# OMNIBUS_EstlCam_board_v3.net
KiCad netlist of a schematic drawn in EAGLE
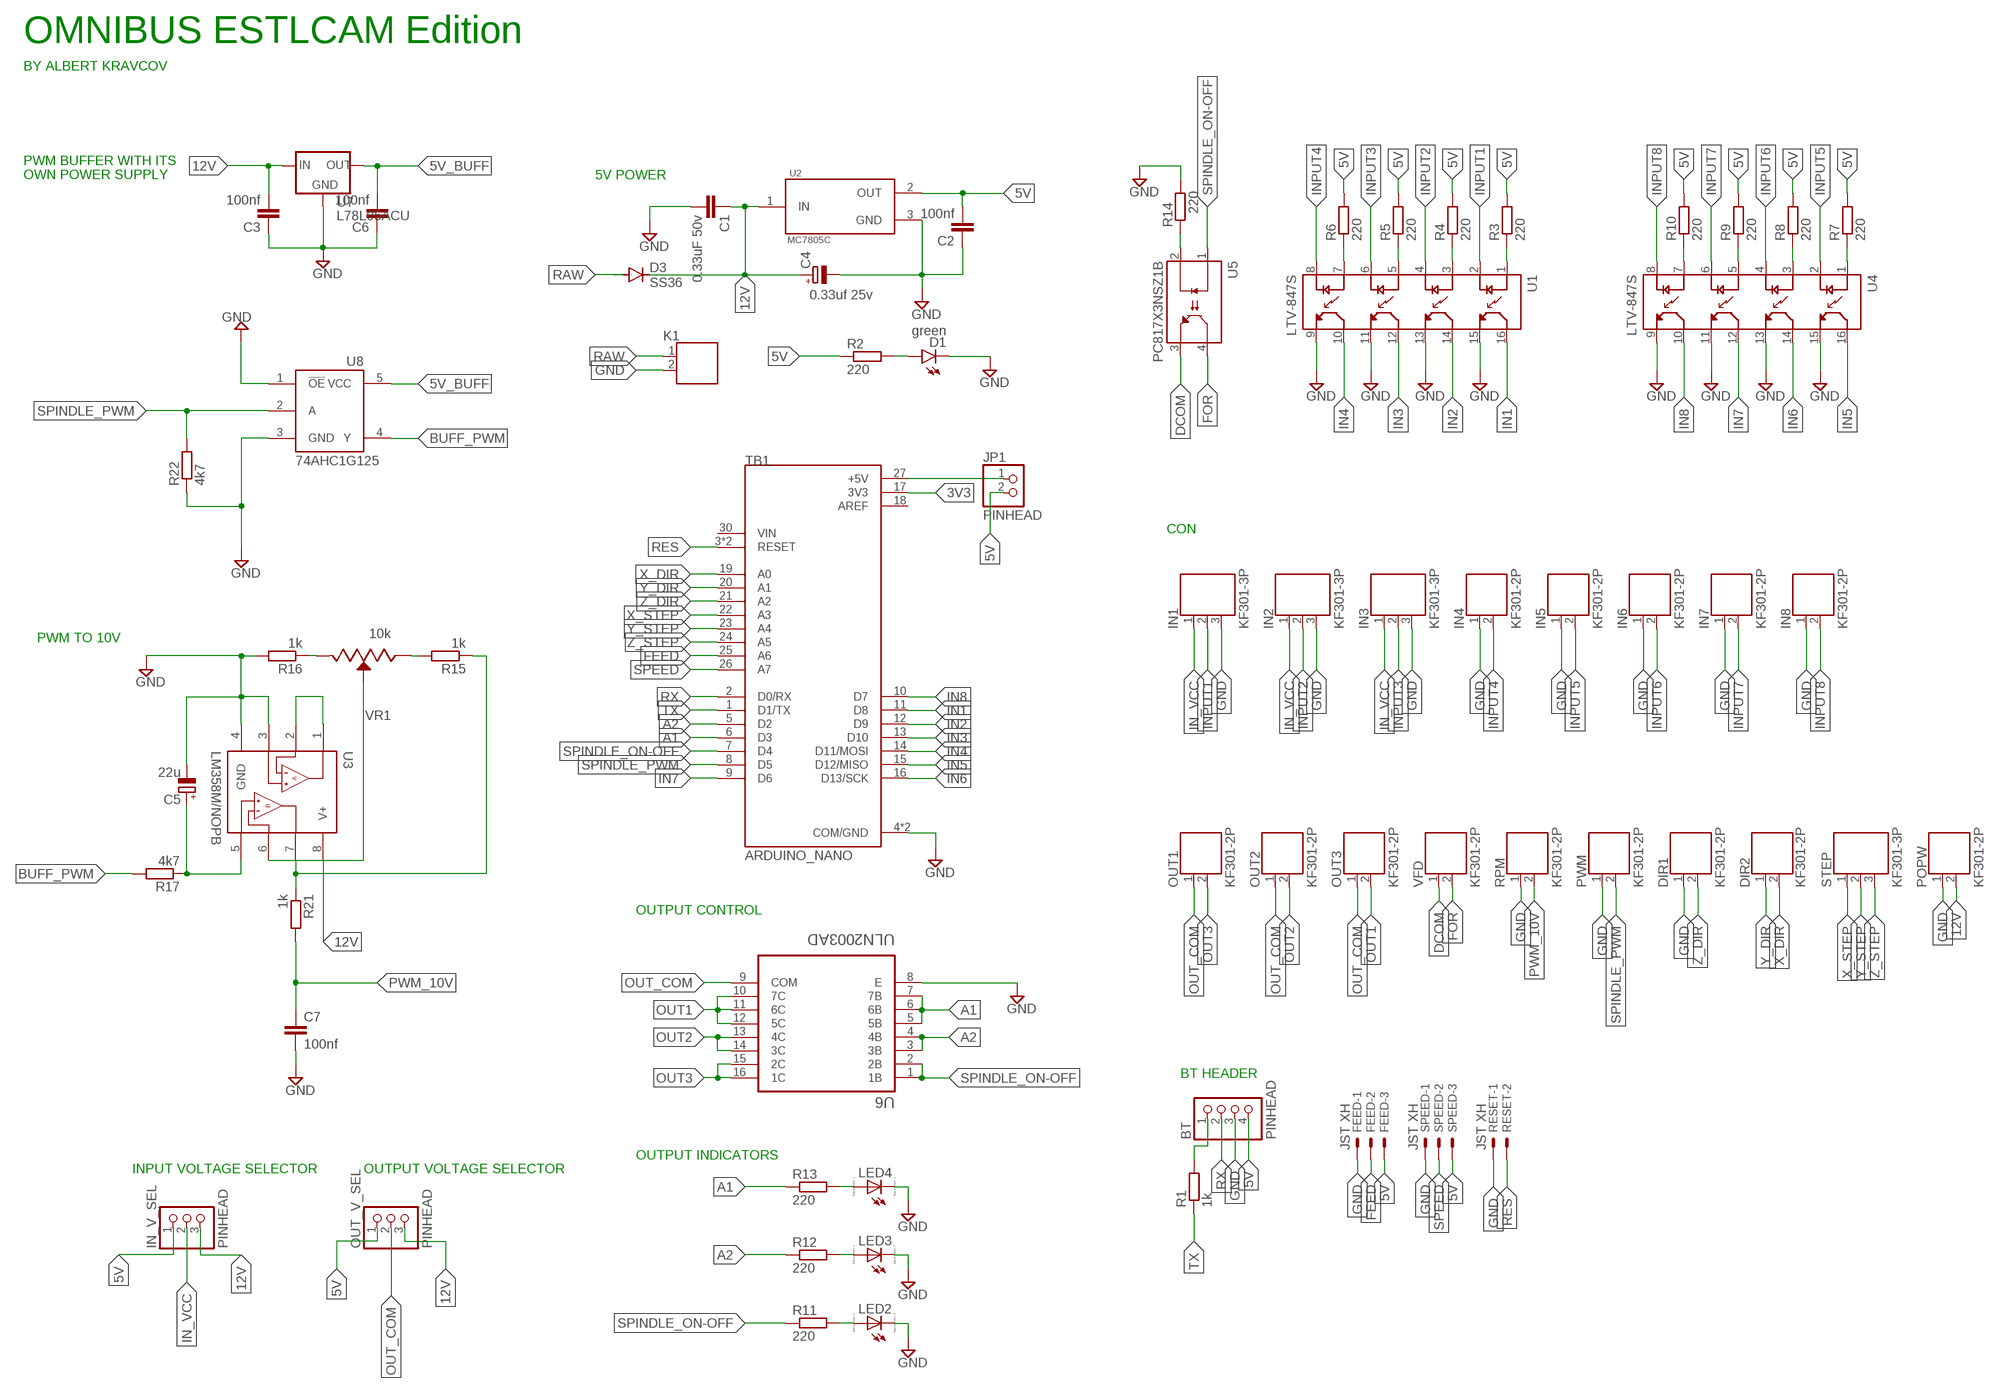
[diagram p0: schematic, sheet 1]

(export (version "E")
  (design (tool "Eeschema 10.0.6"))
  (components
    (comp (ref "BT")
      (value "PINHEAD")
      (footprint "eagle-import:1X04")
      (libsource (lib "eagle-import") (part "PINHD-1X4"))
    )
    (comp (ref "C1")
      (value "0.33uF 50v")
      (footprint "eagle-import:C1206")
      (libsource (lib "eagle-import") (part "C-EUC1206"))
    )
    (comp (ref "C2")
      (value "100nf")
      (footprint "eagle-import:C0805")
      (libsource (lib "eagle-import") (part "C-EUC0805"))
    )
    (comp (ref "C3")
      (value "100nf")
      (footprint "eagle-import:C0805")
      (libsource (lib "eagle-import") (part "C-EUC0805"))
    )
    (comp (ref "C4")
      (value "0.33uf 25v")
      (footprint "eagle-import:E2-5")
      (libsource (lib "eagle-import") (part "CPOL-EUE2-5"))
    )
    (comp (ref "C5")
      (value "22u")
      (footprint "eagle-import:E2-5")
      (libsource (lib "eagle-import") (part "CPOL-EUE2-5"))
    )
    (comp (ref "C6")
      (value "100nf")
      (footprint "eagle-import:C0805")
      (libsource (lib "eagle-import") (part "C-EUC0805"))
    )
    (comp (ref "C7")
      (value "100nf")
      (footprint "eagle-import:C0805")
      (libsource (lib "eagle-import") (part "C-EUC0805"))
    )
    (comp (ref "D1")
      (value "green")
      (footprint "eagle-import:CHIPLED_0805")
      (libsource (lib "eagle-import") (part "LEDCHIPLED_0805"))
    )
    (comp (ref "D3")
      (value "SS36")
      (footprint "eagle-import:SMB")
      (libsource (lib "eagle-import") (part "ES2D"))
    )
    (comp (ref "DIR1")
      (value "KF301-2P")
      (footprint "eagle-import:691131710002")
      (libsource (lib "eagle-import") (part "691131710002"))
    )
    (comp (ref "DIR2")
      (value "KF301-2P")
      (footprint "eagle-import:691131710002")
      (libsource (lib "eagle-import") (part "691131710002"))
    )
    (comp (ref "FEED")
      (value "JST XH")
      (footprint "eagle-import:22-23-2031")
      (fields (field (name "MF") "MOLEX") (field (name "MPN") "22-23-2031"))
      (libsource (lib "eagle-import") (part "22-23-2031"))
    )
    (comp (ref "IN1")
      (value "KF301-3P")
      (footprint "eagle-import:691131710003")
      (libsource (lib "eagle-import") (part "691131710003"))
    )
    (comp (ref "IN2")
      (value "KF301-3P")
      (footprint "eagle-import:691131710003")
      (libsource (lib "eagle-import") (part "691131710003"))
    )
    (comp (ref "IN3")
      (value "KF301-3P")
      (footprint "eagle-import:691131710003")
      (libsource (lib "eagle-import") (part "691131710003"))
    )
    (comp (ref "IN4")
      (value "KF301-2P")
      (footprint "eagle-import:691131710002")
      (libsource (lib "eagle-import") (part "691131710002"))
    )
    (comp (ref "IN5")
      (value "KF301-2P")
      (footprint "eagle-import:691131710002")
      (libsource (lib "eagle-import") (part "691131710002"))
    )
    (comp (ref "IN6")
      (value "KF301-2P")
      (footprint "eagle-import:691131710002")
      (libsource (lib "eagle-import") (part "691131710002"))
    )
    (comp (ref "IN7")
      (value "KF301-2P")
      (footprint "eagle-import:691131710002")
      (libsource (lib "eagle-import") (part "691131710002"))
    )
    (comp (ref "IN8")
      (value "KF301-2P")
      (footprint "eagle-import:691131710002")
      (libsource (lib "eagle-import") (part "691131710002"))
    )
    (comp (ref "IN_V_SEL")
      (value "PINHEAD")
      (footprint "eagle-import:1X03")
      (libsource (lib "eagle-import") (part "PINHD-1X3"))
    )
    (comp (ref "JP1")
      (value "PINHEAD")
      (footprint "eagle-import:1X02")
      (libsource (lib "eagle-import") (part "PINHD-1X2"))
    )
    (comp (ref "K1")
      (value "691131710002")
      (footprint "eagle-import:691131710002")
      (libsource (lib "eagle-import") (part "691131710002"))
    )
    (comp (ref "LED2")
      (value "LED_ESML0603")
      (footprint "eagle-import:LED_SML0603")
      (libsource (lib "eagle-import") (part "LED_ESML0603"))
    )
    (comp (ref "LED3")
      (value "LED_ESML0603")
      (footprint "eagle-import:LED_SML0603")
      (libsource (lib "eagle-import") (part "LED_ESML0603"))
    )
    (comp (ref "LED4")
      (value "LED_ESML0603")
      (footprint "eagle-import:LED_SML0603")
      (libsource (lib "eagle-import") (part "LED_ESML0603"))
    )
    (comp (ref "OUT1")
      (value "KF301-2P")
      (footprint "eagle-import:691131710002")
      (libsource (lib "eagle-import") (part "691131710002"))
    )
    (comp (ref "OUT2")
      (value "KF301-2P")
      (footprint "eagle-import:691131710002")
      (libsource (lib "eagle-import") (part "691131710002"))
    )
    (comp (ref "OUT3")
      (value "KF301-2P")
      (footprint "eagle-import:691131710002")
      (libsource (lib "eagle-import") (part "691131710002"))
    )
    (comp (ref "OUT_V_SEL")
      (value "PINHEAD")
      (footprint "eagle-import:1X03")
      (libsource (lib "eagle-import") (part "PINHD-1X3"))
    )
    (comp (ref "POPW")
      (value "KF301-2P")
      (footprint "eagle-import:691131710002")
      (libsource (lib "eagle-import") (part "691131710002"))
    )
    (comp (ref "PWM")
      (value "KF301-2P")
      (footprint "eagle-import:691131710002")
      (libsource (lib "eagle-import") (part "691131710002"))
    )
    (comp (ref "R1")
      (value "1k")
      (footprint "eagle-import:R0805")
      (libsource (lib "eagle-import") (part "R-EU_R0805"))
    )
    (comp (ref "R2")
      (value "220")
      (footprint "eagle-import:R0805")
      (libsource (lib "eagle-import") (part "R-EU_R0805"))
    )
    (comp (ref "R3")
      (value "220")
      (footprint "eagle-import:R0805")
      (libsource (lib "eagle-import") (part "R-EU_R0805"))
    )
    (comp (ref "R4")
      (value "220")
      (footprint "eagle-import:R0805")
      (libsource (lib "eagle-import") (part "R-EU_R0805"))
    )
    (comp (ref "R5")
      (value "220")
      (footprint "eagle-import:R0805")
      (libsource (lib "eagle-import") (part "R-EU_R0805"))
    )
    (comp (ref "R6")
      (value "220")
      (footprint "eagle-import:R0805")
      (libsource (lib "eagle-import") (part "R-EU_R0805"))
    )
    (comp (ref "R7")
      (value "220")
      (footprint "eagle-import:R0805")
      (libsource (lib "eagle-import") (part "R-EU_R0805"))
    )
    (comp (ref "R8")
      (value "220")
      (footprint "eagle-import:R0805")
      (libsource (lib "eagle-import") (part "R-EU_R0805"))
    )
    (comp (ref "R9")
      (value "220")
      (footprint "eagle-import:R0805")
      (libsource (lib "eagle-import") (part "R-EU_R0805"))
    )
    (comp (ref "R10")
      (value "220")
      (footprint "eagle-import:R0805")
      (libsource (lib "eagle-import") (part "R-EU_R0805"))
    )
    (comp (ref "R11")
      (value "220")
      (footprint "eagle-import:R0603")
      (libsource (lib "eagle-import") (part "R-EU_R0603"))
    )
    (comp (ref "R12")
      (value "220")
      (footprint "eagle-import:R0603")
      (libsource (lib "eagle-import") (part "R-EU_R0603"))
    )
    (comp (ref "R13")
      (value "220")
      (footprint "eagle-import:R0603")
      (libsource (lib "eagle-import") (part "R-EU_R0603"))
    )
    (comp (ref "R14")
      (value "220")
      (footprint "eagle-import:R0805")
      (libsource (lib "eagle-import") (part "R-EU_R0805"))
    )
    (comp (ref "R15")
      (value "1k")
      (footprint "eagle-import:R0805")
      (libsource (lib "eagle-import") (part "R-EU_R0805"))
    )
    (comp (ref "R16")
      (value "1k")
      (footprint "eagle-import:R0805")
      (libsource (lib "eagle-import") (part "R-EU_R0805"))
    )
    (comp (ref "R17")
      (value "4k7")
      (footprint "eagle-import:R0603")
      (libsource (lib "eagle-import") (part "R-EU_R0603"))
    )
    (comp (ref "R21")
      (value "1k")
      (footprint "eagle-import:R0805")
      (libsource (lib "eagle-import") (part "R-EU_R0805"))
    )
    (comp (ref "R22")
      (value "4k7")
      (footprint "eagle-import:R0805")
      (libsource (lib "eagle-import") (part "R-EU_R0805"))
    )
    (comp (ref "RESET")
      (value "JST XH")
      (footprint "eagle-import:22-23-2021")
      (fields (field (name "MF") "MOLEX") (field (name "MPN") "22-23-2021"))
      (libsource (lib "eagle-import") (part "22-23-2021"))
    )
    (comp (ref "RPM")
      (value "KF301-2P")
      (footprint "eagle-import:691131710002")
      (libsource (lib "eagle-import") (part "691131710002"))
    )
    (comp (ref "SPEED")
      (value "JST XH")
      (footprint "eagle-import:22-23-2031")
      (fields (field (name "MF") "MOLEX") (field (name "MPN") "22-23-2031"))
      (libsource (lib "eagle-import") (part "22-23-2031"))
    )
    (comp (ref "STEP")
      (value "KF301-3P")
      (footprint "eagle-import:691131710003")
      (libsource (lib "eagle-import") (part "691131710003"))
    )
    (comp (ref "TB1")
      (value "ARDUINO_NANO")
      (footprint "eagle-import:SHIELD_ARDUINO_NANO")
      (fields (field (name "MF") "Arduino") (field (name "MP") "ARDUINO NANO"))
      (libsource (lib "eagle-import") (part "ARDUINO_NANO"))
    )
    (comp (ref "U1")
      (value "LTV-847S")
      (footprint "eagle-import:SOIC254P1016X460-16N")
      (fields (field (name "MF") "Lite-On Inc."))
      (libsource (lib "eagle-import") (part "LTV-847S"))
    )
    (comp (ref "U2")
      (value "MC7805C")
      (footprint "eagle-import:TO254P1515X470-3N")
      (fields (field (name "MF") "STMicroelectronics") (field (name "MP") "L7805ACD2T-TR"))
      (libsource (lib "eagle-import") (part "L7805ACD2T-TR"))
    )
    (comp (ref "U3")
      (value "LM358M/NOPB")
      (footprint "eagle-import:SOIC127P599X175-8N")
      (fields (field (name "MF") "Texas Instruments") (field (name "MP") "LM358M"))
      (libsource (lib "eagle-import") (part "LM358M/NOPB"))
    )
    (comp (ref "U4")
      (value "LTV-847S")
      (footprint "eagle-import:SOIC254P1016X460-16N")
      (fields (field (name "MF") "Lite-On Inc."))
      (libsource (lib "eagle-import") (part "LTV-847S"))
    )
    (comp (ref "U5")
      (value "PC817X3NSZ1B")
      (footprint "eagle-import:DIP762W50P254L495H455Q4")
      (fields (field (name "MF") "Sharp Microelectronics"))
      (libsource (lib "eagle-import") (part "PC817X3NSZ1B"))
    )
    (comp (ref "U6")
      (value "ULN2003AD")
      (footprint "eagle-import:SOIC127P600X175-16N")
      (fields (field (name "MF") "Texas Instruments"))
      (libsource (lib "eagle-import") (part "ULN2003AD"))
    )
    (comp (ref "U7")
      (value "L78L05ACU")
      (footprint "eagle-import:SOT89")
      (fields (field (name "MF") "STMicroelectronics"))
      (libsource (lib "eagle-import") (part "L78L05ACU"))
    )
    (comp (ref "U8")
      (value "74AHC1G125")
      (footprint "eagle-import:SOT23-5L")
      (fields (field (name "MF") "Texas Instruments"))
      (libsource (lib "eagle-import") (part "74AHC1G125"))
    )
    (comp (ref "VFD")
      (value "KF301-2P")
      (footprint "eagle-import:691131710002")
      (libsource (lib "eagle-import") (part "691131710002"))
    )
    (comp (ref "VR1")
      (value "10k")
      (footprint "eagle-import:TRIM_3296W-1-502")
      (fields (field (name "MF") "Bourns") (field (name "MP") "3296W-1-502"))
      (libsource (lib "eagle-import") (part "3296W-1-502"))
    )
  )
  (nets
    (net (code "1") (name "/AREF") (class "Default")
      (node (ref "TB1") (pin "18") (pinfunction "AREF_18") (pintype "power_in"))
    )
    (net (code "2") (name "3V3") (class "Default")
      (node (ref "TB1") (pin "17") (pinfunction "3V3_17") (pintype "power_in"))
    )
    (net (code "3") (name "5V") (class "Default")
      (node (ref "BT") (pin "4") (pinfunction "4_4") (pintype "passive"))
      (node (ref "C2") (pin "2") (pinfunction "2_2") (pintype "passive"))
      (node (ref "FEED") (pin "3") (pinfunction "S_3") (pintype "passive"))
      (node (ref "IN_V_SEL") (pin "1") (pinfunction "1_1") (pintype "passive"))
      (node (ref "JP1") (pin "2") (pinfunction "2_2") (pintype "passive"))
      (node (ref "OUT_V_SEL") (pin "1") (pinfunction "1_1") (pintype "passive"))
      (node (ref "R10") (pin "2") (pinfunction "2_2") (pintype "passive"))
      (node (ref "R2") (pin "1") (pinfunction "1_1") (pintype "passive"))
      (node (ref "R3") (pin "2") (pinfunction "2_2") (pintype "passive"))
      (node (ref "R4") (pin "2") (pinfunction "2_2") (pintype "passive"))
      (node (ref "R5") (pin "2") (pinfunction "2_2") (pintype "passive"))
      (node (ref "R6") (pin "2") (pinfunction "2_2") (pintype "passive"))
      (node (ref "R7") (pin "2") (pinfunction "2_2") (pintype "passive"))
      (node (ref "R8") (pin "2") (pinfunction "2_2") (pintype "passive"))
      (node (ref "R9") (pin "2") (pinfunction "2_2") (pintype "passive"))
      (node (ref "SPEED") (pin "3") (pinfunction "S_3") (pintype "passive"))
      (node (ref "U2") (pin "2") (pinfunction "OUT_2") (pintype "output"))
    )
    (net (code "4") (name "5V_BUFF") (class "Default")
      (node (ref "C6") (pin "2") (pinfunction "2_2") (pintype "passive"))
      (node (ref "U7") (pin "1") (pinfunction "OUT_1") (pintype "output"))
      (node (ref "U8") (pin "5") (pinfunction "VCC_5") (pintype "power_in"))
    )
    (net (code "5") (name "12V") (class "Default")
      (node (ref "C1") (pin "1") (pinfunction "1_1") (pintype "passive"))
      (node (ref "C3") (pin "2") (pinfunction "2_2") (pintype "passive"))
      (node (ref "C4") (pin "+") (pinfunction "+_+") (pintype "passive"))
      (node (ref "D3") (pin "C") (pinfunction "C_C") (pintype "passive"))
      (node (ref "IN_V_SEL") (pin "3") (pinfunction "3_3") (pintype "passive"))
      (node (ref "OUT_V_SEL") (pin "3") (pinfunction "3_3") (pintype "passive"))
      (node (ref "POPW") (pin "2") (pinfunction "2_2") (pintype "passive"))
      (node (ref "U2") (pin "1") (pinfunction "IN_1") (pintype "input"))
      (node (ref "U3") (pin "8") (pinfunction "V+_8") (pintype "power_in"))
      (node (ref "U7") (pin "3") (pinfunction "IN_3") (pintype "input"))
    )
    (net (code "6") (name "A1") (class "Default")
      (node (ref "R13") (pin "1") (pinfunction "1_1") (pintype "passive"))
      (node (ref "TB1") (pin "6") (pinfunction "D3_6") (pintype "bidirectional"))
      (node (ref "U6") (pin "5") (pinfunction "5B_5") (pintype "input"))
      (node (ref "U6") (pin "6") (pinfunction "6B_6") (pintype "input"))
      (node (ref "U6") (pin "7") (pinfunction "7B_7") (pintype "input"))
    )
    (net (code "7") (name "A2") (class "Default")
      (node (ref "R12") (pin "1") (pinfunction "1_1") (pintype "passive"))
      (node (ref "TB1") (pin "5") (pinfunction "D2_5") (pintype "bidirectional"))
      (node (ref "U6") (pin "3") (pinfunction "3B_3") (pintype "input"))
      (node (ref "U6") (pin "4") (pinfunction "4B_4") (pintype "input"))
    )
    (net (code "8") (name "BUFF_PWM") (class "Default")
      (node (ref "R17") (pin "2") (pinfunction "2_2") (pintype "passive"))
      (node (ref "U8") (pin "4") (pinfunction "Y_4") (pintype "output"))
    )
    (net (code "9") (name "DCOM") (class "Default")
      (node (ref "U5") (pin "3") (pinfunction "EMITTER_3") (pintype "passive"))
      (node (ref "VFD") (pin "1") (pinfunction "1_1") (pintype "passive"))
    )
    (net (code "10") (name "FEED") (class "Default")
      (node (ref "FEED") (pin "2") (pinfunction "S_2") (pintype "passive"))
      (node (ref "TB1") (pin "25") (pinfunction "A6_25") (pintype "input"))
    )
    (net (code "11") (name "FOR") (class "Default")
      (node (ref "U5") (pin "4") (pinfunction "COLLECTOR_4") (pintype "passive"))
      (node (ref "VFD") (pin "2") (pinfunction "2_2") (pintype "passive"))
    )
    (net (code "12") (name "GND") (class "Default")
      (node (ref "BT") (pin "3") (pinfunction "3_3") (pintype "passive"))
      (node (ref "C1") (pin "2") (pinfunction "2_2") (pintype "passive"))
      (node (ref "C2") (pin "1") (pinfunction "1_1") (pintype "passive"))
      (node (ref "C3") (pin "1") (pinfunction "1_1") (pintype "passive"))
      (node (ref "C4") (pin "-") (pinfunction "-_-") (pintype "passive"))
      (node (ref "C5") (pin "-") (pinfunction "-_-") (pintype "passive"))
      (node (ref "C6") (pin "1") (pinfunction "1_1") (pintype "passive"))
      (node (ref "C7") (pin "2") (pinfunction "2_2") (pintype "passive"))
      (node (ref "D1") (pin "C") (pinfunction "C_C") (pintype "passive"))
      (node (ref "DIR1") (pin "1") (pinfunction "1_1") (pintype "passive"))
      (node (ref "FEED") (pin "1") (pinfunction "S_1") (pintype "passive"))
      (node (ref "IN1") (pin "3") (pinfunction "3_3") (pintype "passive"))
      (node (ref "IN2") (pin "3") (pinfunction "3_3") (pintype "passive"))
      (node (ref "IN3") (pin "3") (pinfunction "3_3") (pintype "passive"))
      (node (ref "IN4") (pin "1") (pinfunction "1_1") (pintype "passive"))
      (node (ref "IN5") (pin "1") (pinfunction "1_1") (pintype "passive"))
      (node (ref "IN6") (pin "1") (pinfunction "1_1") (pintype "passive"))
      (node (ref "IN7") (pin "1") (pinfunction "1_1") (pintype "passive"))
      (node (ref "IN8") (pin "1") (pinfunction "1_1") (pintype "passive"))
      (node (ref "K1") (pin "2") (pinfunction "2_2") (pintype "passive"))
      (node (ref "LED2") (pin "C") (pinfunction "C_C") (pintype "passive"))
      (node (ref "LED3") (pin "C") (pinfunction "C_C") (pintype "passive"))
      (node (ref "LED4") (pin "C") (pinfunction "C_C") (pintype "passive"))
      (node (ref "POPW") (pin "1") (pinfunction "1_1") (pintype "passive"))
      (node (ref "PWM") (pin "1") (pinfunction "1_1") (pintype "passive"))
      (node (ref "R14") (pin "2") (pinfunction "2_2") (pintype "passive"))
      (node (ref "R16") (pin "2") (pinfunction "2_2") (pintype "passive"))
      (node (ref "R22") (pin "1") (pinfunction "1_1") (pintype "passive"))
      (node (ref "RESET") (pin "1") (pinfunction "S_1") (pintype "passive"))
      (node (ref "RPM") (pin "1") (pinfunction "1_1") (pintype "passive"))
      (node (ref "SPEED") (pin "1") (pinfunction "S_1") (pintype "passive"))
      (node (ref "TB1") (pin "29") (pinfunction "COM/GND_29") (pintype "power_in"))
      (node (ref "TB1") (pin "4") (pinfunction "COM/GND_4") (pintype "power_in"))
      (node (ref "U1") (pin "11") (pinfunction "ET2_11") (pintype "passive"))
      (node (ref "U1") (pin "13") (pinfunction "ET1_13") (pintype "passive"))
      (node (ref "U1") (pin "15") (pinfunction "ET_15") (pintype "passive"))
      (node (ref "U1") (pin "9") (pinfunction "ET3_9") (pintype "passive"))
      (node (ref "U2") (pin "3") (pinfunction "GND_3") (pintype "power_in"))
      (node (ref "U3") (pin "3") (pinfunction "+INA_3") (pintype "input"))
      (node (ref "U3") (pin "4") (pinfunction "GND_4") (pintype "power_in"))
      (node (ref "U4") (pin "11") (pinfunction "ET2_11") (pintype "passive"))
      (node (ref "U4") (pin "13") (pinfunction "ET1_13") (pintype "passive"))
      (node (ref "U4") (pin "15") (pinfunction "ET_15") (pintype "passive"))
      (node (ref "U4") (pin "9") (pinfunction "ET3_9") (pintype "passive"))
      (node (ref "U6") (pin "8") (pinfunction "E_8") (pintype "input"))
      (node (ref "U7") (pin "2") (pinfunction "GND_2") (pintype "input"))
      (node (ref "U8") (pin "1") (pinfunction "~{OE}_1") (pintype "input"))
      (node (ref "U8") (pin "3") (pinfunction "GND_3") (pintype "power_in"))
    )
    (net (code "13") (name "IN1") (class "Default")
      (node (ref "TB1") (pin "11") (pinfunction "D8_11") (pintype "bidirectional"))
      (node (ref "U1") (pin "16") (pinfunction "CT_16") (pintype "passive"))
    )
    (net (code "14") (name "IN2") (class "Default")
      (node (ref "TB1") (pin "12") (pinfunction "D9_12") (pintype "bidirectional"))
      (node (ref "U1") (pin "14") (pinfunction "CT1_14") (pintype "passive"))
    )
    (net (code "15") (name "IN3") (class "Default")
      (node (ref "TB1") (pin "13") (pinfunction "D10_13") (pintype "bidirectional"))
      (node (ref "U1") (pin "12") (pinfunction "CT2_12") (pintype "passive"))
    )
    (net (code "16") (name "IN4") (class "Default")
      (node (ref "TB1") (pin "14") (pinfunction "D11/MOSI_14") (pintype "bidirectional"))
      (node (ref "U1") (pin "10") (pinfunction "CT3_10") (pintype "passive"))
    )
    (net (code "17") (name "IN5") (class "Default")
      (node (ref "TB1") (pin "15") (pinfunction "D12/MISO_15") (pintype "bidirectional"))
      (node (ref "U4") (pin "16") (pinfunction "CT_16") (pintype "passive"))
    )
    (net (code "18") (name "IN6") (class "Default")
      (node (ref "TB1") (pin "16") (pinfunction "D13/SCK_16") (pintype "bidirectional"))
      (node (ref "U4") (pin "14") (pinfunction "CT1_14") (pintype "passive"))
    )
    (net (code "19") (name "IN7") (class "Default")
      (node (ref "TB1") (pin "9") (pinfunction "D6_9") (pintype "bidirectional"))
      (node (ref "U4") (pin "12") (pinfunction "CT2_12") (pintype "passive"))
    )
    (net (code "20") (name "IN8") (class "Default")
      (node (ref "TB1") (pin "10") (pinfunction "D7_10") (pintype "bidirectional"))
      (node (ref "U4") (pin "10") (pinfunction "CT3_10") (pintype "passive"))
    )
    (net (code "21") (name "INPUT1") (class "Default")
      (node (ref "IN1") (pin "2") (pinfunction "2_2") (pintype "passive"))
      (node (ref "U1") (pin "2") (pinfunction "C_2") (pintype "passive"))
    )
    (net (code "22") (name "INPUT2") (class "Default")
      (node (ref "IN2") (pin "2") (pinfunction "2_2") (pintype "passive"))
      (node (ref "U1") (pin "4") (pinfunction "C1_4") (pintype "passive"))
    )
    (net (code "23") (name "INPUT3") (class "Default")
      (node (ref "IN3") (pin "2") (pinfunction "2_2") (pintype "passive"))
      (node (ref "U1") (pin "6") (pinfunction "C2_6") (pintype "passive"))
    )
    (net (code "24") (name "INPUT4") (class "Default")
      (node (ref "IN4") (pin "2") (pinfunction "2_2") (pintype "passive"))
      (node (ref "U1") (pin "8") (pinfunction "C3_8") (pintype "passive"))
    )
    (net (code "25") (name "INPUT5") (class "Default")
      (node (ref "IN5") (pin "2") (pinfunction "2_2") (pintype "passive"))
      (node (ref "U4") (pin "2") (pinfunction "C_2") (pintype "passive"))
    )
    (net (code "26") (name "INPUT6") (class "Default")
      (node (ref "IN6") (pin "2") (pinfunction "2_2") (pintype "passive"))
      (node (ref "U4") (pin "4") (pinfunction "C1_4") (pintype "passive"))
    )
    (net (code "27") (name "INPUT7") (class "Default")
      (node (ref "IN7") (pin "2") (pinfunction "2_2") (pintype "passive"))
      (node (ref "U4") (pin "6") (pinfunction "C2_6") (pintype "passive"))
    )
    (net (code "28") (name "INPUT8") (class "Default")
      (node (ref "IN8") (pin "2") (pinfunction "2_2") (pintype "passive"))
      (node (ref "U4") (pin "8") (pinfunction "C3_8") (pintype "passive"))
    )
    (net (code "29") (name "IN_VCC") (class "Default")
      (node (ref "IN1") (pin "1") (pinfunction "1_1") (pintype "passive"))
      (node (ref "IN2") (pin "1") (pinfunction "1_1") (pintype "passive"))
      (node (ref "IN3") (pin "1") (pinfunction "1_1") (pintype "passive"))
      (node (ref "IN_V_SEL") (pin "2") (pinfunction "2_2") (pintype "passive"))
    )
    (net (code "30") (name "Net-(BT-Pad1)") (class "Default")
      (node (ref "BT") (pin "1") (pinfunction "1_1") (pintype "passive"))
      (node (ref "R1") (pin "2") (pinfunction "2_2") (pintype "passive"))
    )
    (net (code "31") (name "Net-(D1-PadA)") (class "Default")
      (node (ref "D1") (pin "A") (pinfunction "A_A") (pintype "passive"))
      (node (ref "R2") (pin "2") (pinfunction "2_2") (pintype "passive"))
    )
    (net (code "32") (name "Net-(LED2-PadA)") (class "Default")
      (node (ref "LED2") (pin "A") (pinfunction "A_A") (pintype "passive"))
      (node (ref "R11") (pin "2") (pinfunction "2_2") (pintype "passive"))
    )
    (net (code "33") (name "Net-(LED3-PadA)") (class "Default")
      (node (ref "LED3") (pin "A") (pinfunction "A_A") (pintype "passive"))
      (node (ref "R12") (pin "2") (pinfunction "2_2") (pintype "passive"))
    )
    (net (code "34") (name "Net-(LED4-PadA)") (class "Default")
      (node (ref "LED4") (pin "A") (pinfunction "A_A") (pintype "passive"))
      (node (ref "R13") (pin "2") (pinfunction "2_2") (pintype "passive"))
    )
    (net (code "35") (name "Net-(TB1-+5V)") (class "Default")
      (node (ref "JP1") (pin "1") (pinfunction "1_1") (pintype "passive"))
      (node (ref "TB1") (pin "27") (pinfunction "+5V_27") (pintype "power_in"))
    )
    (net (code "36") (name "Net-(U1-A)") (class "Default")
      (node (ref "R3") (pin "1") (pinfunction "1_1") (pintype "passive"))
      (node (ref "U1") (pin "1") (pinfunction "A_1") (pintype "passive"))
    )
    (net (code "37") (name "Net-(U1-A1)") (class "Default")
      (node (ref "R4") (pin "1") (pinfunction "1_1") (pintype "passive"))
      (node (ref "U1") (pin "3") (pinfunction "A1_3") (pintype "passive"))
    )
    (net (code "38") (name "Net-(U1-A2)") (class "Default")
      (node (ref "R5") (pin "1") (pinfunction "1_1") (pintype "passive"))
      (node (ref "U1") (pin "5") (pinfunction "A2_5") (pintype "passive"))
    )
    (net (code "39") (name "Net-(U1-A3)") (class "Default")
      (node (ref "R6") (pin "1") (pinfunction "1_1") (pintype "passive"))
      (node (ref "U1") (pin "7") (pinfunction "A3_7") (pintype "passive"))
    )
    (net (code "40") (name "Net-(U3-+INB)") (class "Default")
      (node (ref "C5") (pin "+") (pinfunction "+_+") (pintype "passive"))
      (node (ref "R17") (pin "1") (pinfunction "1_1") (pintype "passive"))
      (node (ref "U3") (pin "5") (pinfunction "+INB_5") (pintype "input"))
    )
    (net (code "41") (name "Net-(U3--INA)") (class "Default")
      (node (ref "U3") (pin "1") (pinfunction "OUTA_1") (pintype "output"))
      (node (ref "U3") (pin "2") (pinfunction "-INA_2") (pintype "input"))
    )
    (net (code "42") (name "Net-(U3--INB)") (class "Default")
      (node (ref "U3") (pin "6") (pinfunction "-INB_6") (pintype "input"))
      (node (ref "VR1") (pin "2") (pinfunction "WIPER_2") (pintype "passive"))
    )
    (net (code "43") (name "Net-(U3-OUTB)") (class "Default")
      (node (ref "R15") (pin "1") (pinfunction "1_1") (pintype "passive"))
      (node (ref "R21") (pin "1") (pinfunction "1_1") (pintype "passive"))
      (node (ref "U3") (pin "7") (pinfunction "OUTB_7") (pintype "output"))
    )
    (net (code "44") (name "Net-(U4-A)") (class "Default")
      (node (ref "R7") (pin "1") (pinfunction "1_1") (pintype "passive"))
      (node (ref "U4") (pin "1") (pinfunction "A_1") (pintype "passive"))
    )
    (net (code "45") (name "Net-(U4-A1)") (class "Default")
      (node (ref "R8") (pin "1") (pinfunction "1_1") (pintype "passive"))
      (node (ref "U4") (pin "3") (pinfunction "A1_3") (pintype "passive"))
    )
    (net (code "46") (name "Net-(U4-A2)") (class "Default")
      (node (ref "R9") (pin "1") (pinfunction "1_1") (pintype "passive"))
      (node (ref "U4") (pin "5") (pinfunction "A2_5") (pintype "passive"))
    )
    (net (code "47") (name "Net-(U4-A3)") (class "Default")
      (node (ref "R10") (pin "1") (pinfunction "1_1") (pintype "passive"))
      (node (ref "U4") (pin "7") (pinfunction "A3_7") (pintype "passive"))
    )
    (net (code "48") (name "Net-(U5-CATHODE)") (class "Default")
      (node (ref "R14") (pin "1") (pinfunction "1_1") (pintype "passive"))
      (node (ref "U5") (pin "2") (pinfunction "CATHODE_2") (pintype "passive"))
    )
    (net (code "49") (name "Net-(VR1-CCW)") (class "Default")
      (node (ref "R15") (pin "2") (pinfunction "2_2") (pintype "passive"))
      (node (ref "VR1") (pin "1") (pinfunction "CCW_1") (pintype "passive"))
    )
    (net (code "50") (name "Net-(VR1-CW)") (class "Default")
      (node (ref "R16") (pin "1") (pinfunction "1_1") (pintype "passive"))
      (node (ref "VR1") (pin "3") (pinfunction "CW_3") (pintype "passive"))
    )
    (net (code "51") (name "OUT1") (class "Default")
      (node (ref "OUT3") (pin "2") (pinfunction "2_2") (pintype "passive"))
      (node (ref "U6") (pin "10") (pinfunction "7C_10") (pintype "output"))
      (node (ref "U6") (pin "11") (pinfunction "6C_11") (pintype "output"))
      (node (ref "U6") (pin "12") (pinfunction "5C_12") (pintype "output"))
    )
    (net (code "52") (name "OUT2") (class "Default")
      (node (ref "OUT2") (pin "2") (pinfunction "2_2") (pintype "passive"))
      (node (ref "U6") (pin "13") (pinfunction "4C_13") (pintype "output"))
      (node (ref "U6") (pin "14") (pinfunction "3C_14") (pintype "output"))
    )
    (net (code "53") (name "OUT3") (class "Default")
      (node (ref "OUT1") (pin "2") (pinfunction "2_2") (pintype "passive"))
      (node (ref "U6") (pin "15") (pinfunction "2C_15") (pintype "output"))
      (node (ref "U6") (pin "16") (pinfunction "1C_16") (pintype "output"))
    )
    (net (code "54") (name "OUT_COM") (class "Default")
      (node (ref "OUT1") (pin "1") (pinfunction "1_1") (pintype "passive"))
      (node (ref "OUT2") (pin "1") (pinfunction "1_1") (pintype "passive"))
      (node (ref "OUT3") (pin "1") (pinfunction "1_1") (pintype "passive"))
      (node (ref "OUT_V_SEL") (pin "2") (pinfunction "2_2") (pintype "passive"))
      (node (ref "U6") (pin "9") (pinfunction "COM_9") (pintype "output"))
    )
    (net (code "55") (name "PWM_10V") (class "Default")
      (node (ref "C7") (pin "1") (pinfunction "1_1") (pintype "passive"))
      (node (ref "R21") (pin "2") (pinfunction "2_2") (pintype "passive"))
      (node (ref "RPM") (pin "2") (pinfunction "2_2") (pintype "passive"))
    )
    (net (code "56") (name "RAW") (class "Default")
      (node (ref "D3") (pin "A") (pinfunction "A_A") (pintype "passive"))
      (node (ref "K1") (pin "1") (pinfunction "1_1") (pintype "passive"))
    )
    (net (code "57") (name "RES") (class "Default")
      (node (ref "RESET") (pin "2") (pinfunction "S_2") (pintype "passive"))
      (node (ref "TB1") (pin "28") (pinfunction "RESET_28") (pintype "input"))
      (node (ref "TB1") (pin "3") (pinfunction "RESET_3") (pintype "input"))
    )
    (net (code "58") (name "RX") (class "Default")
      (node (ref "BT") (pin "2") (pinfunction "2_2") (pintype "passive"))
      (node (ref "TB1") (pin "2") (pinfunction "D0/RX_2") (pintype "bidirectional"))
    )
    (net (code "59") (name "SPEED") (class "Default")
      (node (ref "SPEED") (pin "2") (pinfunction "S_2") (pintype "passive"))
      (node (ref "TB1") (pin "26") (pinfunction "A7_26") (pintype "input"))
    )
    (net (code "60") (name "SPINDLE_ON-OFF") (class "Default")
      (node (ref "R11") (pin "1") (pinfunction "1_1") (pintype "passive"))
      (node (ref "TB1") (pin "7") (pinfunction "D4_7") (pintype "bidirectional"))
      (node (ref "U5") (pin "1") (pinfunction "ANODE_1") (pintype "passive"))
      (node (ref "U6") (pin "1") (pinfunction "1B_1") (pintype "input"))
      (node (ref "U6") (pin "2") (pinfunction "2B_2") (pintype "input"))
    )
    (net (code "61") (name "SPINDLE_PWM") (class "Default")
      (node (ref "PWM") (pin "2") (pinfunction "2_2") (pintype "passive"))
      (node (ref "R22") (pin "2") (pinfunction "2_2") (pintype "passive"))
      (node (ref "TB1") (pin "8") (pinfunction "D5_8") (pintype "bidirectional"))
      (node (ref "U8") (pin "2") (pinfunction "A_2") (pintype "input"))
    )
    (net (code "62") (name "TX") (class "Default")
      (node (ref "R1") (pin "1") (pinfunction "1_1") (pintype "passive"))
      (node (ref "TB1") (pin "1") (pinfunction "D1/TX_1") (pintype "bidirectional"))
    )
    (net (code "63") (name "X_DIR") (class "Default")
      (node (ref "DIR2") (pin "2") (pinfunction "2_2") (pintype "passive"))
      (node (ref "TB1") (pin "19") (pinfunction "A0_19") (pintype "input"))
    )
    (net (code "64") (name "X_STEP") (class "Default")
      (node (ref "STEP") (pin "1") (pinfunction "1_1") (pintype "passive"))
      (node (ref "TB1") (pin "22") (pinfunction "A3_22") (pintype "input"))
    )
    (net (code "65") (name "Y_DIR") (class "Default")
      (node (ref "DIR2") (pin "1") (pinfunction "1_1") (pintype "passive"))
      (node (ref "TB1") (pin "20") (pinfunction "A1_20") (pintype "input"))
    )
    (net (code "66") (name "Y_STEP") (class "Default")
      (node (ref "STEP") (pin "2") (pinfunction "2_2") (pintype "passive"))
      (node (ref "TB1") (pin "23") (pinfunction "A4_23") (pintype "input"))
    )
    (net (code "67") (name "Z_DIR") (class "Default")
      (node (ref "DIR1") (pin "2") (pinfunction "2_2") (pintype "passive"))
      (node (ref "TB1") (pin "21") (pinfunction "A2_21") (pintype "input"))
    )
    (net (code "68") (name "Z_STEP") (class "Default")
      (node (ref "STEP") (pin "3") (pinfunction "3_3") (pintype "passive"))
      (node (ref "TB1") (pin "24") (pinfunction "A5_24") (pintype "input"))
    )
    (net (code "69") (name "unconnected-(TB1-VIN-Pad30)") (class "Default")
      (node (ref "TB1") (pin "30") (pinfunction "VIN_30") (pintype "input"))
    )
  )
)
